# TSOC_Teensy3X.net
KiCad netlist of a schematic drawn in EAGLE
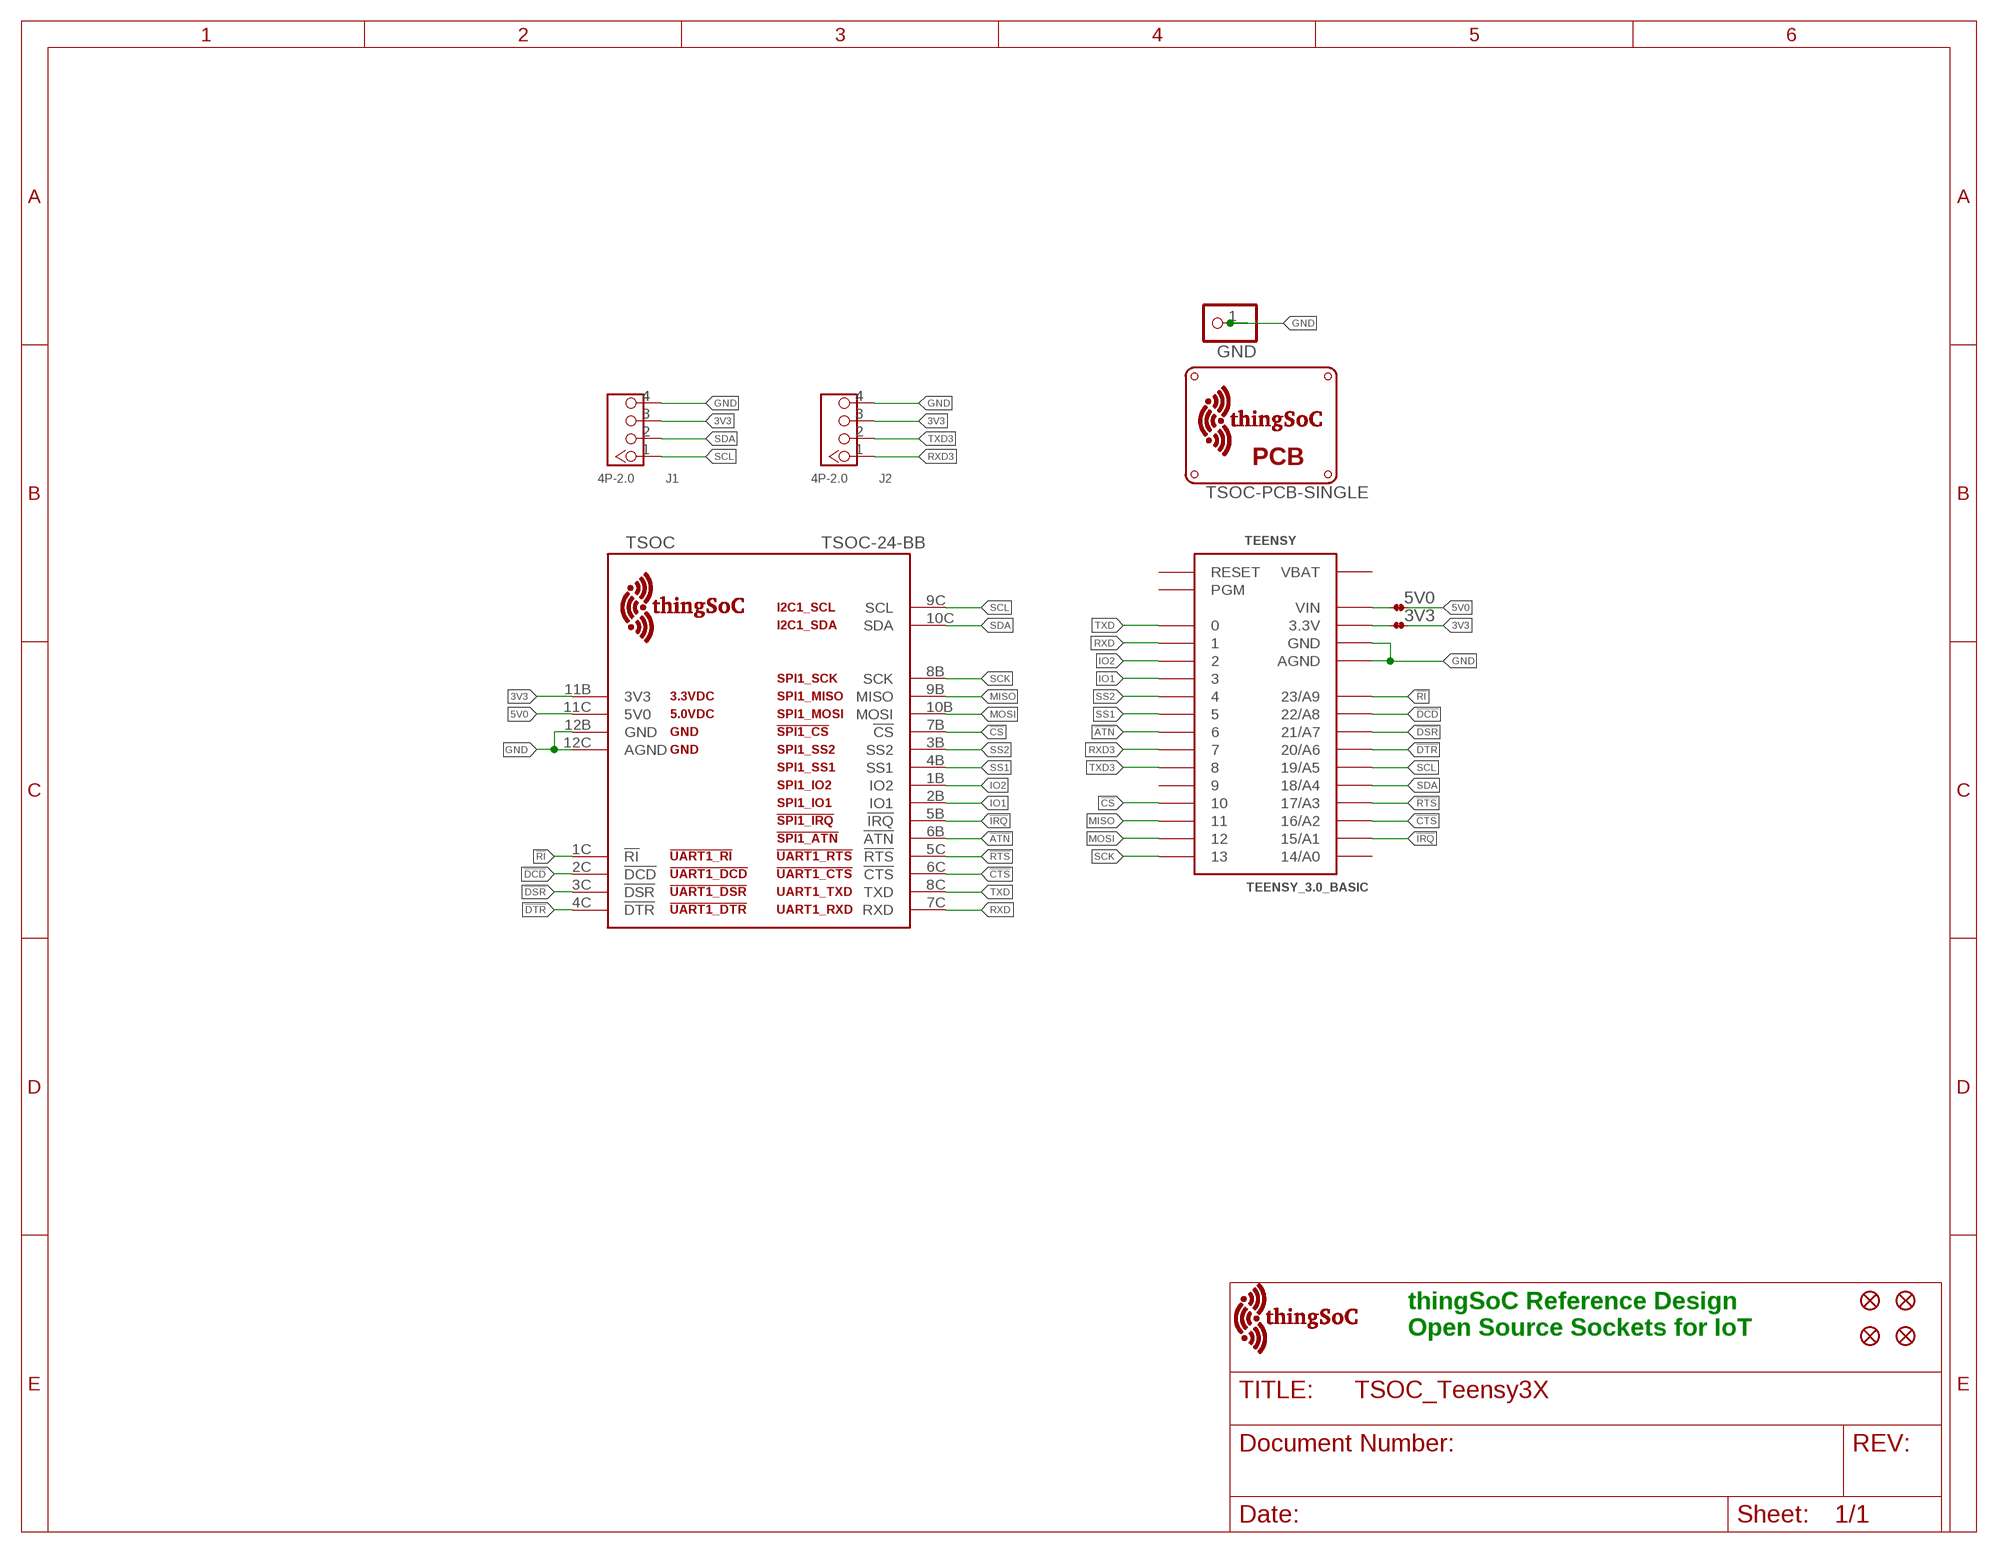
[diagram p0: schematic, sheet 1]

(export (version "E")
  (design (tool "Eeschema 10.0.6"))
  (components
    (comp (ref "3V3")
      (value "JMP-2-NC")
      (footprint "eagle-import:JMP-2-NC")
      (libsource (lib "eagle-import") (part "JMP-2-NC"))
    )
    (comp (ref "5V0")
      (value "JMP-2-NC")
      (footprint "eagle-import:JMP-2-NC")
      (libsource (lib "eagle-import") (part "JMP-2-NC"))
    )
    (comp (ref "FID1")
      (value "FIDUCIALUFIDUCIAL")
      (footprint "eagle-import:MICRO-FIDUCIAL")
      (libsource (lib "eagle-import") (part "FIDUCIALUFIDUCIAL"))
    )
    (comp (ref "FID2")
      (value "FIDUCIALUFIDUCIAL")
      (footprint "eagle-import:MICRO-FIDUCIAL")
      (libsource (lib "eagle-import") (part "FIDUCIALUFIDUCIAL"))
    )
    (comp (ref "FID3")
      (value "FIDUCIALUFIDUCIAL")
      (footprint "eagle-import:MICRO-FIDUCIAL")
      (libsource (lib "eagle-import") (part "FIDUCIALUFIDUCIAL"))
    )
    (comp (ref "FID4")
      (value "FIDUCIALUFIDUCIAL")
      (footprint "eagle-import:MICRO-FIDUCIAL")
      (libsource (lib "eagle-import") (part "FIDUCIALUFIDUCIAL"))
    )
    (comp (ref "GND")
      (value "WPAD-1-PTH")
      (footprint "eagle-import:WPAD-1-PTH-2.54")
      (libsource (lib "eagle-import") (part "WPAD-1-PTH"))
    )
    (comp (ref "J1")
      (value "4P-2.0")
      (footprint "eagle-import:HW4-2.0")
      (libsource (lib "eagle-import") (part "GROVE-CONNECTOR-DIP(4P-2.0)"))
    )
    (comp (ref "J2")
      (value "4P-2.0")
      (footprint "eagle-import:HW4-2.0")
      (libsource (lib "eagle-import") (part "GROVE-CONNECTOR-DIP(4P-2.0)"))
    )
    (comp (ref "TEENSY")
      (value "TEENSY_3.0_BASIC")
      (footprint "eagle-import:TEENSY_3.0_BASIC")
      (libsource (lib "eagle-import") (part "TEENSY_3.0_BASIC"))
    )
    (comp (ref "TSOC")
      (value "TSOC-24-BB")
      (footprint "eagle-import:TSOC-BB-S24")
      (libsource (lib "eagle-import") (part "TSOC-24-BB"))
    )
    (comp (ref "U$2")
      (value "TSOC-PCB-SINGLE")
      (footprint "eagle-import:TSOC-BB-BRD-DIM")
      (libsource (lib "eagle-import") (part "TSOC-PCB-SINGLE"))
    )
    (comp (ref "U$5")
      (value "TSOC-LOGO-LRG")
      (footprint "eagle-import:TSOC-LOGO-LRG")
      (libsource (lib "eagle-import") (part "TSOC-LOGO-LRG"))
    )
  )
  (nets
    (net (code "1") (name "/VBAT") (class "Default")
      (node (ref "TEENSY") (pin "VBAT") (pinfunction "VBAT_VBAT") (pintype "power_in"))
    )
    (net (code "2") (name "/~{ATN}") (class "Default")
      (node (ref "TEENSY") (pin "6") (pinfunction "6_6") (pintype "bidirectional"))
      (node (ref "TSOC") (pin "6B") (pinfunction "~{ATN}_6B") (pintype "bidirectional"))
    )
    (net (code "3") (name "/~{CS}") (class "Default")
      (node (ref "TEENSY") (pin "10") (pinfunction "10_10") (pintype "bidirectional"))
      (node (ref "TSOC") (pin "7B") (pinfunction "~{CS}_7B") (pintype "bidirectional"))
    )
    (net (code "4") (name "/~{CTS}") (class "Default")
      (node (ref "TEENSY") (pin "16/A2") (pinfunction "16/A2_16/A2") (pintype "bidirectional"))
      (node (ref "TSOC") (pin "6C") (pinfunction "~{CTS}_6C") (pintype "bidirectional"))
    )
    (net (code "5") (name "/~{DCD}") (class "Default")
      (node (ref "TEENSY") (pin "22/A8") (pinfunction "22/A8_22/A8") (pintype "bidirectional"))
      (node (ref "TSOC") (pin "2C") (pinfunction "~{DCD}_2C") (pintype "bidirectional"))
    )
    (net (code "6") (name "/~{DSR}") (class "Default")
      (node (ref "TEENSY") (pin "21/A7") (pinfunction "21/A7_21/A7") (pintype "bidirectional"))
      (node (ref "TSOC") (pin "3C") (pinfunction "~{DSR}_3C") (pintype "bidirectional"))
    )
    (net (code "7") (name "/~{DTR}") (class "Default")
      (node (ref "TEENSY") (pin "20/A6") (pinfunction "20/A6_20/A6") (pintype "bidirectional"))
      (node (ref "TSOC") (pin "4C") (pinfunction "~{DTR}_4C") (pintype "bidirectional"))
    )
    (net (code "8") (name "/~{IRQ}") (class "Default")
      (node (ref "TEENSY") (pin "15/A1") (pinfunction "15/A1_15/A1") (pintype "bidirectional"))
      (node (ref "TSOC") (pin "5B") (pinfunction "~{IRQ}_5B") (pintype "bidirectional"))
    )
    (net (code "9") (name "/~{RI}") (class "Default")
      (node (ref "TEENSY") (pin "23/A9") (pinfunction "23/A9_23/A9") (pintype "bidirectional"))
      (node (ref "TSOC") (pin "1C") (pinfunction "~{RI}_1C") (pintype "bidirectional"))
    )
    (net (code "10") (name "/~{RTS}") (class "Default")
      (node (ref "TEENSY") (pin "17/A3") (pinfunction "17/A3_17/A3") (pintype "bidirectional"))
      (node (ref "TSOC") (pin "5C") (pinfunction "~{RTS}_5C") (pintype "bidirectional"))
    )
    (net (code "11") (name "3V3") (class "Default")
      (node (ref "3V3") (pin "2") (pinfunction "2_2") (pintype "passive"))
      (node (ref "J1") (pin "3") (pinfunction "3_3") (pintype "bidirectional"))
      (node (ref "J2") (pin "3") (pinfunction "3_3") (pintype "bidirectional"))
      (node (ref "TSOC") (pin "11B") (pinfunction "3V3_11B") (pintype "bidirectional"))
    )
    (net (code "12") (name "5V0") (class "Default")
      (node (ref "5V0") (pin "2") (pinfunction "2_2") (pintype "passive"))
      (node (ref "TSOC") (pin "11C") (pinfunction "5V0_11C") (pintype "bidirectional"))
    )
    (net (code "13") (name "GND") (class "Default")
      (node (ref "GND") (pin "1") (pinfunction "1_1") (pintype "passive"))
      (node (ref "J1") (pin "4") (pinfunction "4_4") (pintype "bidirectional"))
      (node (ref "J2") (pin "4") (pinfunction "4_4") (pintype "bidirectional"))
      (node (ref "TEENSY") (pin "AGND") (pinfunction "AGND_AGND") (pintype "power_in"))
      (node (ref "TEENSY") (pin "GND") (pinfunction "GND_GND") (pintype "power_in"))
      (node (ref "TEENSY") (pin "GND1") (pinfunction "GND_GND1") (pintype "power_in"))
      (node (ref "TSOC") (pin "12B") (pinfunction "GND_12B") (pintype "bidirectional"))
      (node (ref "TSOC") (pin "12C") (pinfunction "AGND_12C") (pintype "bidirectional"))
    )
    (net (code "14") (name "IO1") (class "Default")
      (node (ref "TEENSY") (pin "3") (pinfunction "3_3") (pintype "bidirectional"))
      (node (ref "TSOC") (pin "2B") (pinfunction "IO1_2B") (pintype "bidirectional"))
    )
    (net (code "15") (name "IO2") (class "Default")
      (node (ref "TEENSY") (pin "2") (pinfunction "2_2") (pintype "bidirectional"))
      (node (ref "TSOC") (pin "1B") (pinfunction "IO2_1B") (pintype "bidirectional"))
    )
    (net (code "16") (name "MISO") (class "Default")
      (node (ref "TEENSY") (pin "11") (pinfunction "11_11") (pintype "bidirectional"))
      (node (ref "TSOC") (pin "9B") (pinfunction "MISO_9B") (pintype "bidirectional"))
    )
    (net (code "17") (name "MOSI") (class "Default")
      (node (ref "TEENSY") (pin "12") (pinfunction "12_12") (pintype "bidirectional"))
      (node (ref "TSOC") (pin "10B") (pinfunction "MOSI_10B") (pintype "bidirectional"))
    )
    (net (code "18") (name "Net-(3V3-Pad1)") (class "Default")
      (node (ref "3V3") (pin "1") (pinfunction "1_1") (pintype "passive"))
      (node (ref "TEENSY") (pin "3.3V") (pinfunction "3.3V_3.3V") (pintype "power_in"))
      (node (ref "TEENSY") (pin "3.3V1") (pinfunction "3.3V_3.3V1") (pintype "power_in"))
    )
    (net (code "19") (name "Net-(5V0-Pad1)") (class "Default")
      (node (ref "5V0") (pin "1") (pinfunction "1_1") (pintype "passive"))
      (node (ref "TEENSY") (pin "VIN") (pinfunction "VIN_VIN") (pintype "power_in"))
    )
    (net (code "20") (name "RXD") (class "Default")
      (node (ref "TEENSY") (pin "1") (pinfunction "1_1") (pintype "bidirectional"))
      (node (ref "TSOC") (pin "7C") (pinfunction "RXD_7C") (pintype "bidirectional"))
    )
    (net (code "21") (name "RXD3") (class "Default")
      (node (ref "J2") (pin "1") (pinfunction "1_1") (pintype "bidirectional"))
      (node (ref "TEENSY") (pin "7") (pinfunction "7_7") (pintype "bidirectional"))
    )
    (net (code "22") (name "SCK") (class "Default")
      (node (ref "TEENSY") (pin "13") (pinfunction "13_13") (pintype "bidirectional"))
      (node (ref "TSOC") (pin "8B") (pinfunction "SCK_8B") (pintype "bidirectional"))
    )
    (net (code "23") (name "SCL") (class "Default")
      (node (ref "J1") (pin "1") (pinfunction "1_1") (pintype "bidirectional"))
      (node (ref "TEENSY") (pin "19/A5") (pinfunction "19/A5_19/A5") (pintype "bidirectional"))
      (node (ref "TSOC") (pin "9C") (pinfunction "SCL_9C") (pintype "bidirectional"))
    )
    (net (code "24") (name "SDA") (class "Default")
      (node (ref "J1") (pin "2") (pinfunction "2_2") (pintype "bidirectional"))
      (node (ref "TEENSY") (pin "18/A4") (pinfunction "18/A4_18/A4") (pintype "bidirectional"))
      (node (ref "TSOC") (pin "10C") (pinfunction "SDA_10C") (pintype "bidirectional"))
    )
    (net (code "25") (name "SS1") (class "Default")
      (node (ref "TEENSY") (pin "5") (pinfunction "5_5") (pintype "bidirectional"))
      (node (ref "TSOC") (pin "4B") (pinfunction "SS1_4B") (pintype "bidirectional"))
    )
    (net (code "26") (name "SS2") (class "Default")
      (node (ref "TEENSY") (pin "4") (pinfunction "4_4") (pintype "bidirectional"))
      (node (ref "TSOC") (pin "3B") (pinfunction "SS2_3B") (pintype "bidirectional"))
    )
    (net (code "27") (name "TXD") (class "Default")
      (node (ref "TEENSY") (pin "0") (pinfunction "0_0") (pintype "bidirectional"))
      (node (ref "TSOC") (pin "8C") (pinfunction "TXD_8C") (pintype "bidirectional"))
    )
    (net (code "28") (name "TXD3") (class "Default")
      (node (ref "J2") (pin "2") (pinfunction "2_2") (pintype "bidirectional"))
      (node (ref "TEENSY") (pin "8") (pinfunction "8_8") (pintype "bidirectional"))
    )
    (net (code "29") (name "unconnected-(TEENSY-Pad9)") (class "Default")
      (node (ref "TEENSY") (pin "9") (pinfunction "9_9") (pintype "bidirectional"))
    )
    (net (code "30") (name "unconnected-(TEENSY-Pad14{slash}A0)") (class "Default")
      (node (ref "TEENSY") (pin "14/A0") (pinfunction "14/A0_14/A0") (pintype "bidirectional"))
    )
    (net (code "31") (name "unconnected-(TEENSY-PadPGM)") (class "Default")
      (node (ref "TEENSY") (pin "PGM") (pinfunction "PGM_PGM") (pintype "bidirectional"))
    )
    (net (code "32") (name "unconnected-(TEENSY-PadRESET)") (class "Default")
      (node (ref "TEENSY") (pin "RESET") (pinfunction "RESET_RESET") (pintype "bidirectional"))
    )
  )
)
